# display_board.net
KiCad netlist of a schematic drawn in EAGLE
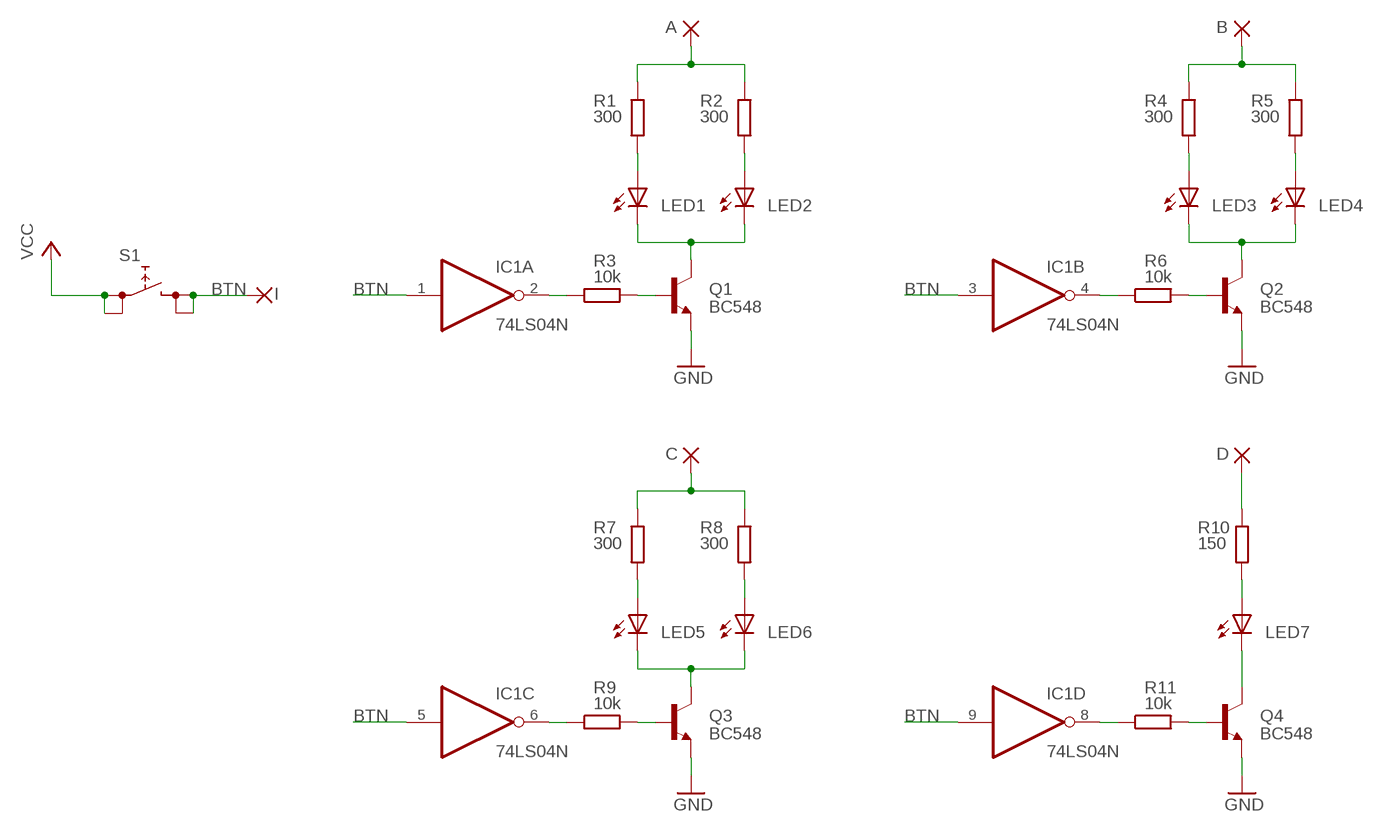
[diagram p0: schematic, sheet 1]

(export (version "E")
  (design (tool "Eeschema 10.0.6"))
  (components
    (comp (ref "A")
      (value "1,6/0,9")
      (footprint "eagle-import:1,6_0,9")
      (libsource (lib "eagle-import") (part "1,6/0,9"))
    )
    (comp (ref "B")
      (value "1,6/0,9")
      (footprint "eagle-import:1,6_0,9")
      (libsource (lib "eagle-import") (part "1,6/0,9"))
    )
    (comp (ref "C")
      (value "1,6/0,9")
      (footprint "eagle-import:1,6_0,9")
      (libsource (lib "eagle-import") (part "1,6/0,9"))
    )
    (comp (ref "D")
      (value "1,6/0,9")
      (footprint "eagle-import:1,6_0,9")
      (libsource (lib "eagle-import") (part "1,6/0,9"))
    )
    (comp (ref "I")
      (value "1,6/0,9")
      (footprint "eagle-import:1,6_0,9")
      (libsource (lib "eagle-import") (part "1,6/0,9"))
    )
    (comp (ref "IC1")
      (value "74LS04N")
      (footprint "eagle-import:DIL14")
      (libsource (lib "eagle-import") (part "7404NLS"))
    )
    (comp (ref "LED1")
      (value "LED3MM")
      (footprint "eagle-import:LED3MM")
      (libsource (lib "eagle-import") (part "LED3MM"))
    )
    (comp (ref "LED2")
      (value "LED3MM")
      (footprint "eagle-import:LED3MM")
      (libsource (lib "eagle-import") (part "LED3MM"))
    )
    (comp (ref "LED3")
      (value "LED3MM")
      (footprint "eagle-import:LED3MM")
      (libsource (lib "eagle-import") (part "LED3MM"))
    )
    (comp (ref "LED4")
      (value "LED3MM")
      (footprint "eagle-import:LED3MM")
      (libsource (lib "eagle-import") (part "LED3MM"))
    )
    (comp (ref "LED5")
      (value "LED3MM")
      (footprint "eagle-import:LED3MM")
      (libsource (lib "eagle-import") (part "LED3MM"))
    )
    (comp (ref "LED6")
      (value "LED3MM")
      (footprint "eagle-import:LED3MM")
      (libsource (lib "eagle-import") (part "LED3MM"))
    )
    (comp (ref "LED7")
      (value "LED3MM")
      (footprint "eagle-import:LED3MM")
      (libsource (lib "eagle-import") (part "LED3MM"))
    )
    (comp (ref "Q1")
      (value "BC548")
      (footprint "eagle-import:TO92-EBC")
      (libsource (lib "eagle-import") (part "BC548"))
    )
    (comp (ref "Q2")
      (value "BC548")
      (footprint "eagle-import:TO92-EBC")
      (libsource (lib "eagle-import") (part "BC548"))
    )
    (comp (ref "Q3")
      (value "BC548")
      (footprint "eagle-import:TO92-EBC")
      (libsource (lib "eagle-import") (part "BC548"))
    )
    (comp (ref "Q4")
      (value "BC548")
      (footprint "eagle-import:TO92-EBC")
      (libsource (lib "eagle-import") (part "BC548"))
    )
    (comp (ref "R1")
      (value "300")
      (footprint "eagle-import:0207_10")
      (libsource (lib "eagle-import") (part "R-EU_0207/10"))
    )
    (comp (ref "R2")
      (value "300")
      (footprint "eagle-import:0207_10")
      (libsource (lib "eagle-import") (part "R-EU_0207/10"))
    )
    (comp (ref "R3")
      (value "10k")
      (footprint "eagle-import:0207_10")
      (libsource (lib "eagle-import") (part "R-EU_0207/10"))
    )
    (comp (ref "R4")
      (value "300")
      (footprint "eagle-import:0207_10")
      (libsource (lib "eagle-import") (part "R-EU_0207/10"))
    )
    (comp (ref "R5")
      (value "300")
      (footprint "eagle-import:0207_10")
      (libsource (lib "eagle-import") (part "R-EU_0207/10"))
    )
    (comp (ref "R6")
      (value "10k")
      (footprint "eagle-import:0207_10")
      (libsource (lib "eagle-import") (part "R-EU_0207/10"))
    )
    (comp (ref "R7")
      (value "300")
      (footprint "eagle-import:0207_10")
      (libsource (lib "eagle-import") (part "R-EU_0207/10"))
    )
    (comp (ref "R8")
      (value "300")
      (footprint "eagle-import:0207_10")
      (libsource (lib "eagle-import") (part "R-EU_0207/10"))
    )
    (comp (ref "R9")
      (value "10k")
      (footprint "eagle-import:0207_10")
      (libsource (lib "eagle-import") (part "R-EU_0207/10"))
    )
    (comp (ref "R10")
      (value "150")
      (footprint "eagle-import:0207_10")
      (libsource (lib "eagle-import") (part "R-EU_0207/10"))
    )
    (comp (ref "R11")
      (value "10k")
      (footprint "eagle-import:0207_10")
      (libsource (lib "eagle-import") (part "R-EU_0207/10"))
    )
    (comp (ref "S1")
      (value "REKN")
      (footprint "eagle-import:REKN")
      (libsource (lib "eagle-import") (part "REKN"))
    )
  )
  (nets
    (net (code "1") (name "/BTN") (class "Default")
      (node (ref "I") (pin "1") (pinfunction "P_1") (pintype "passive"))
      (node (ref "IC1") (pin "1") (pinfunction "I_1") (pintype "input"))
      (node (ref "IC1") (pin "3") (pinfunction "I_3") (pintype "input"))
      (node (ref "IC1") (pin "5") (pinfunction "I_5") (pintype "input"))
      (node (ref "IC1") (pin "9") (pinfunction "I_9") (pintype "input"))
      (node (ref "S1") (pin "1A") (pinfunction "1_1A") (pintype "passive"))
      (node (ref "S1") (pin "1B") (pinfunction "1_1B") (pintype "passive"))
    )
    (net (code "2") (name "GND") (class "Default")
      (node (ref "Q1") (pin "E") (pinfunction "E_E") (pintype "passive"))
      (node (ref "Q2") (pin "E") (pinfunction "E_E") (pintype "passive"))
      (node (ref "Q3") (pin "E") (pinfunction "E_E") (pintype "passive"))
      (node (ref "Q4") (pin "E") (pinfunction "E_E") (pintype "passive"))
    )
    (net (code "3") (name "Net-(A-P)") (class "Default")
      (node (ref "A") (pin "1") (pinfunction "P_1") (pintype "passive"))
      (node (ref "R1") (pin "1") (pinfunction "1_1") (pintype "passive"))
      (node (ref "R2") (pin "1") (pinfunction "1_1") (pintype "passive"))
    )
    (net (code "4") (name "Net-(B-P)") (class "Default")
      (node (ref "B") (pin "1") (pinfunction "P_1") (pintype "passive"))
      (node (ref "R4") (pin "1") (pinfunction "1_1") (pintype "passive"))
      (node (ref "R5") (pin "1") (pinfunction "1_1") (pintype "passive"))
    )
    (net (code "5") (name "Net-(C-P)") (class "Default")
      (node (ref "C") (pin "1") (pinfunction "P_1") (pintype "passive"))
      (node (ref "R7") (pin "1") (pinfunction "1_1") (pintype "passive"))
      (node (ref "R8") (pin "1") (pinfunction "1_1") (pintype "passive"))
    )
    (net (code "6") (name "Net-(D-P)") (class "Default")
      (node (ref "D") (pin "1") (pinfunction "P_1") (pintype "passive"))
      (node (ref "R10") (pin "1") (pinfunction "1_1") (pintype "passive"))
    )
    (net (code "7") (name "Net-(IC1A-O)") (class "Default")
      (node (ref "IC1") (pin "2") (pinfunction "O_2") (pintype "output"))
      (node (ref "R3") (pin "1") (pinfunction "1_1") (pintype "passive"))
    )
    (net (code "8") (name "Net-(IC1B-O)") (class "Default")
      (node (ref "IC1") (pin "4") (pinfunction "O_4") (pintype "output"))
      (node (ref "R6") (pin "1") (pinfunction "1_1") (pintype "passive"))
    )
    (net (code "9") (name "Net-(IC1C-O)") (class "Default")
      (node (ref "IC1") (pin "6") (pinfunction "O_6") (pintype "output"))
      (node (ref "R9") (pin "1") (pinfunction "1_1") (pintype "passive"))
    )
    (net (code "10") (name "Net-(IC1D-O)") (class "Default")
      (node (ref "IC1") (pin "8") (pinfunction "O_8") (pintype "output"))
      (node (ref "R11") (pin "1") (pinfunction "1_1") (pintype "passive"))
    )
    (net (code "11") (name "Net-(LED1-C)") (class "Default")
      (node (ref "LED1") (pin "K") (pinfunction "C_K") (pintype "passive"))
      (node (ref "LED2") (pin "K") (pinfunction "C_K") (pintype "passive"))
      (node (ref "Q1") (pin "C") (pinfunction "C_C") (pintype "passive"))
    )
    (net (code "12") (name "Net-(LED1-PadA)") (class "Default")
      (node (ref "LED1") (pin "A") (pinfunction "A_A") (pintype "passive"))
      (node (ref "R1") (pin "2") (pinfunction "2_2") (pintype "passive"))
    )
    (net (code "13") (name "Net-(LED2-PadA)") (class "Default")
      (node (ref "LED2") (pin "A") (pinfunction "A_A") (pintype "passive"))
      (node (ref "R2") (pin "2") (pinfunction "2_2") (pintype "passive"))
    )
    (net (code "14") (name "Net-(LED3-C)") (class "Default")
      (node (ref "LED3") (pin "K") (pinfunction "C_K") (pintype "passive"))
      (node (ref "LED4") (pin "K") (pinfunction "C_K") (pintype "passive"))
      (node (ref "Q2") (pin "C") (pinfunction "C_C") (pintype "passive"))
    )
    (net (code "15") (name "Net-(LED3-PadA)") (class "Default")
      (node (ref "LED3") (pin "A") (pinfunction "A_A") (pintype "passive"))
      (node (ref "R4") (pin "2") (pinfunction "2_2") (pintype "passive"))
    )
    (net (code "16") (name "Net-(LED4-PadA)") (class "Default")
      (node (ref "LED4") (pin "A") (pinfunction "A_A") (pintype "passive"))
      (node (ref "R5") (pin "2") (pinfunction "2_2") (pintype "passive"))
    )
    (net (code "17") (name "Net-(LED5-C)") (class "Default")
      (node (ref "LED5") (pin "K") (pinfunction "C_K") (pintype "passive"))
      (node (ref "LED6") (pin "K") (pinfunction "C_K") (pintype "passive"))
      (node (ref "Q3") (pin "C") (pinfunction "C_C") (pintype "passive"))
    )
    (net (code "18") (name "Net-(LED5-PadA)") (class "Default")
      (node (ref "LED5") (pin "A") (pinfunction "A_A") (pintype "passive"))
      (node (ref "R7") (pin "2") (pinfunction "2_2") (pintype "passive"))
    )
    (net (code "19") (name "Net-(LED6-PadA)") (class "Default")
      (node (ref "LED6") (pin "A") (pinfunction "A_A") (pintype "passive"))
      (node (ref "R8") (pin "2") (pinfunction "2_2") (pintype "passive"))
    )
    (net (code "20") (name "Net-(LED7-C)") (class "Default")
      (node (ref "LED7") (pin "K") (pinfunction "C_K") (pintype "passive"))
      (node (ref "Q4") (pin "C") (pinfunction "C_C") (pintype "passive"))
    )
    (net (code "21") (name "Net-(LED7-PadA)") (class "Default")
      (node (ref "LED7") (pin "A") (pinfunction "A_A") (pintype "passive"))
      (node (ref "R10") (pin "2") (pinfunction "2_2") (pintype "passive"))
    )
    (net (code "22") (name "Net-(Q1-PadB)") (class "Default")
      (node (ref "Q1") (pin "B") (pinfunction "B_B") (pintype "passive"))
      (node (ref "R3") (pin "2") (pinfunction "2_2") (pintype "passive"))
    )
    (net (code "23") (name "Net-(Q2-PadB)") (class "Default")
      (node (ref "Q2") (pin "B") (pinfunction "B_B") (pintype "passive"))
      (node (ref "R6") (pin "2") (pinfunction "2_2") (pintype "passive"))
    )
    (net (code "24") (name "Net-(Q3-PadB)") (class "Default")
      (node (ref "Q3") (pin "B") (pinfunction "B_B") (pintype "passive"))
      (node (ref "R9") (pin "2") (pinfunction "2_2") (pintype "passive"))
    )
    (net (code "25") (name "Net-(Q4-PadB)") (class "Default")
      (node (ref "Q4") (pin "B") (pinfunction "B_B") (pintype "passive"))
      (node (ref "R11") (pin "2") (pinfunction "2_2") (pintype "passive"))
    )
    (net (code "26") (name "VCC") (class "Default")
      (node (ref "S1") (pin "0A") (pinfunction "0_0A") (pintype "passive"))
      (node (ref "S1") (pin "0B") (pinfunction "0_0B") (pintype "passive"))
    )
  )
)
